# Shield-Proteco.net
KiCad netlist of a schematic drawn in EAGLE
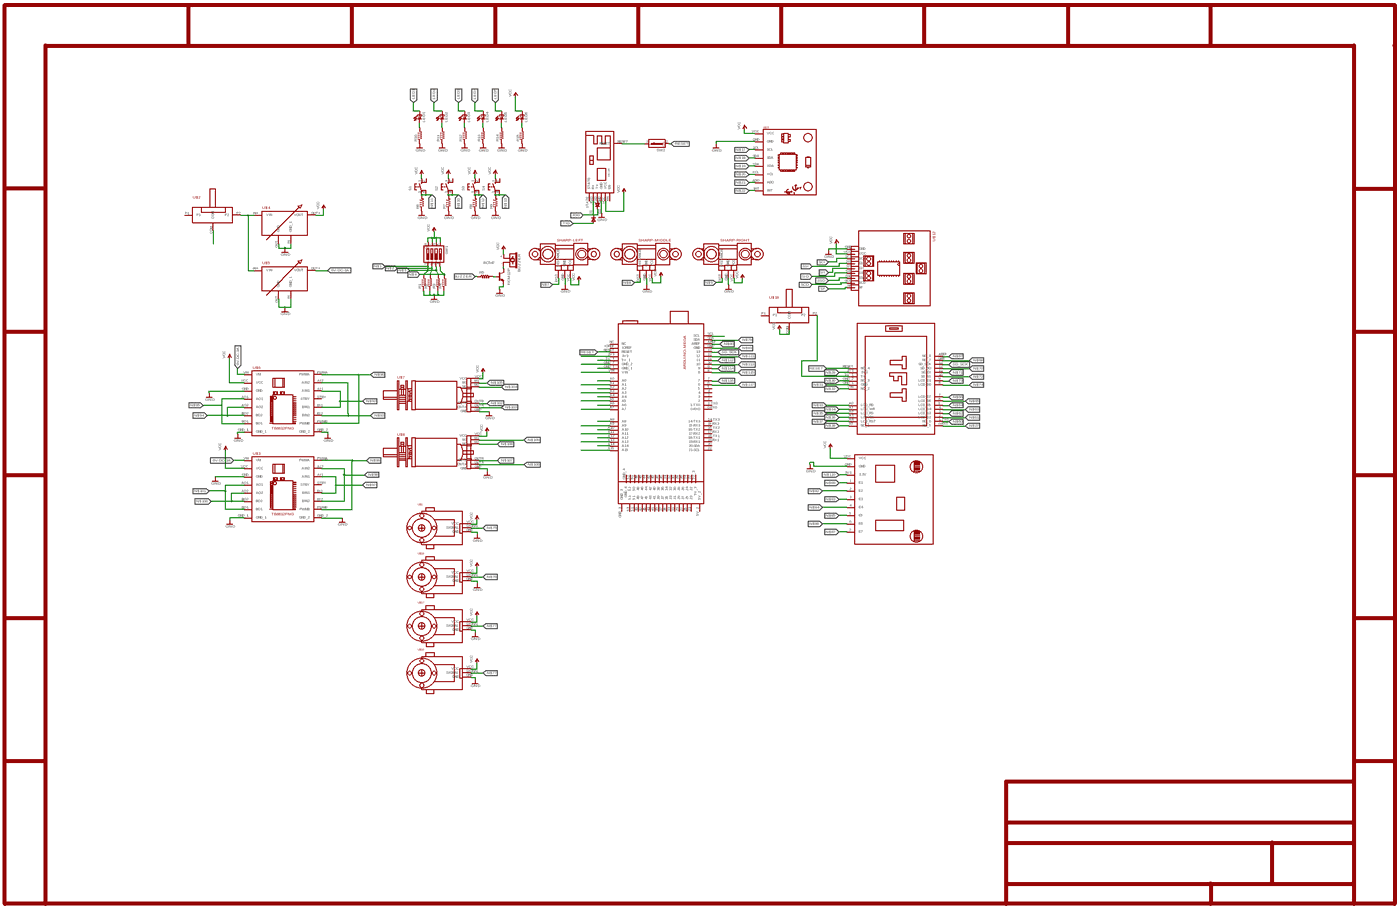
[diagram p0: schematic, sheet 1, overview]
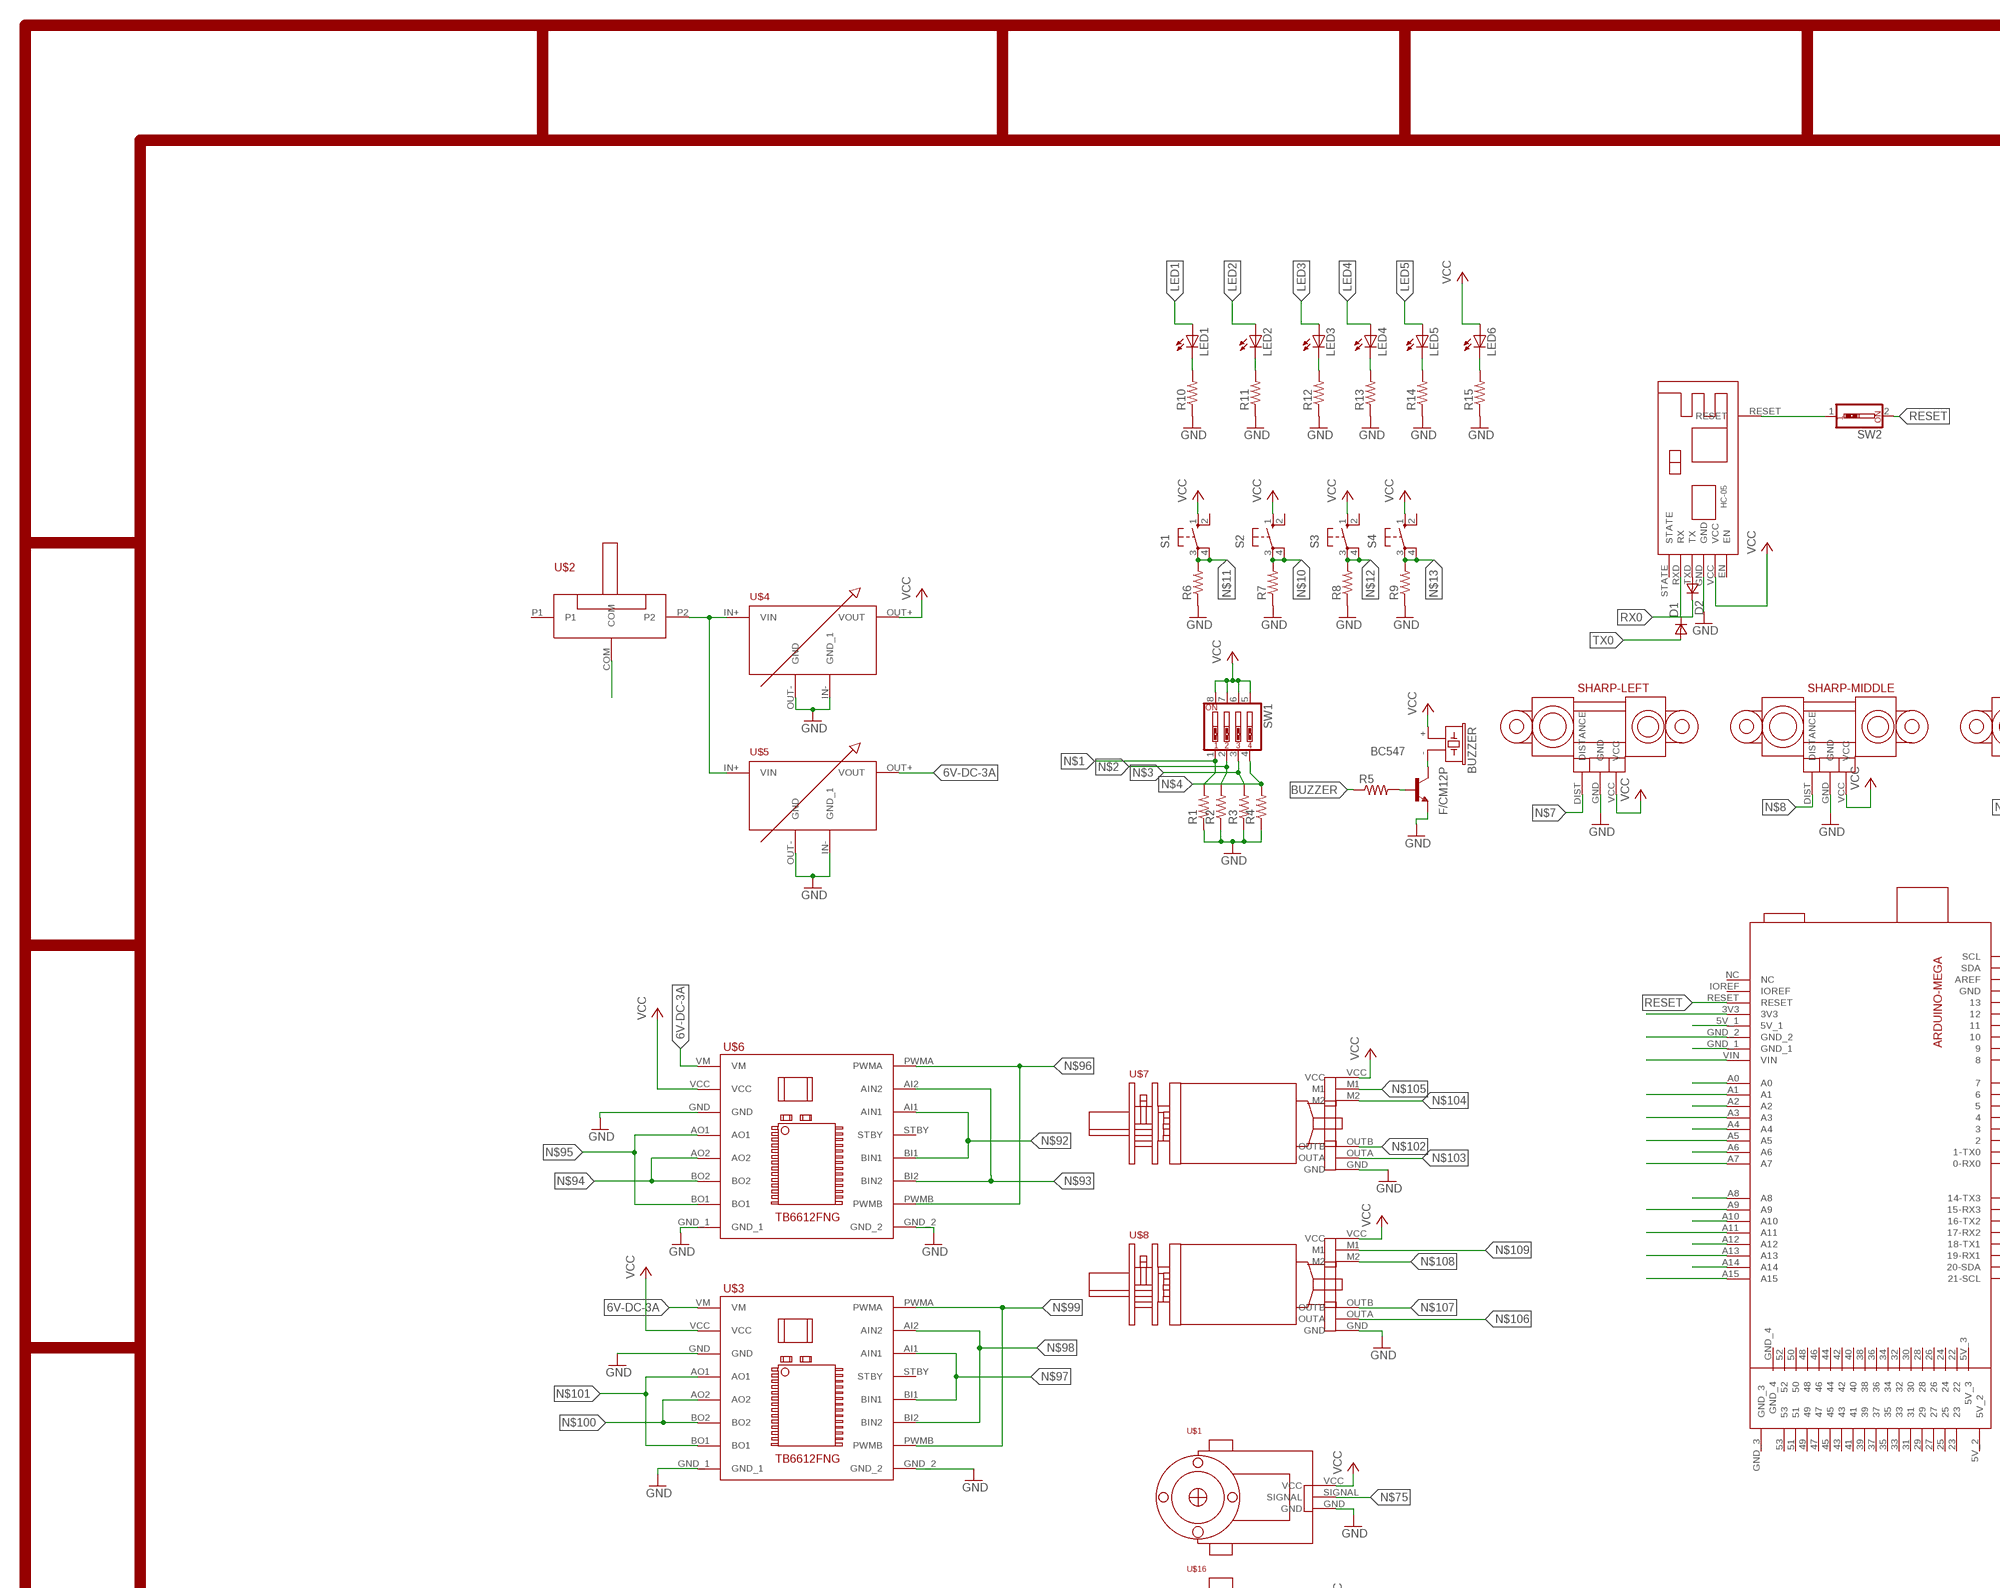
[diagram p1: schematic, sheet 1, part 1 of 4]
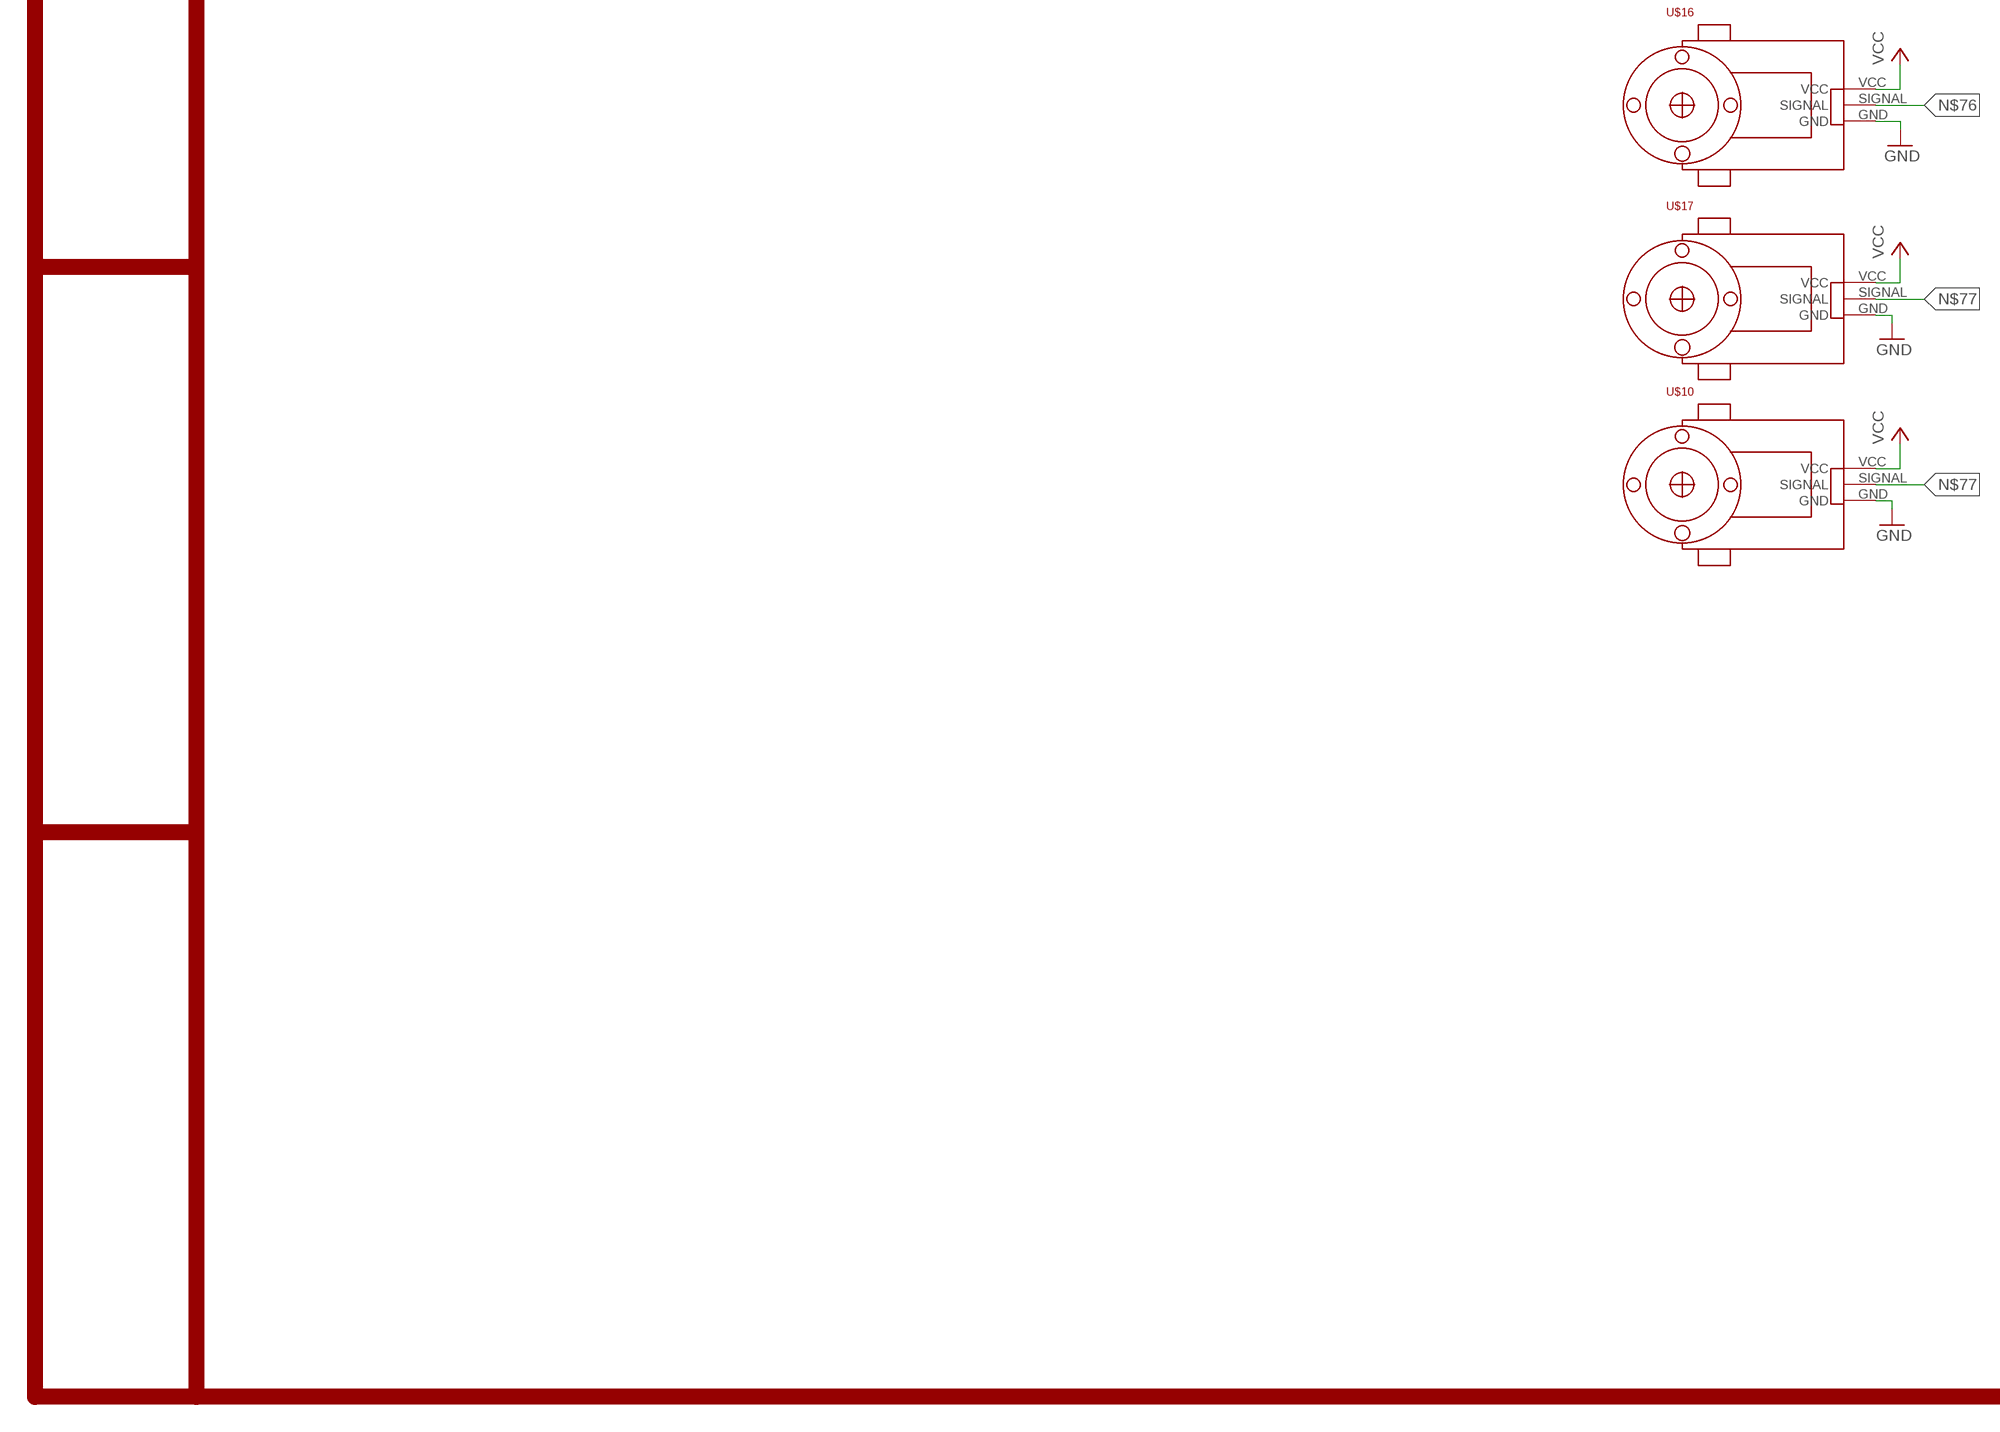
[diagram p2: schematic, sheet 1, part 2 of 4]
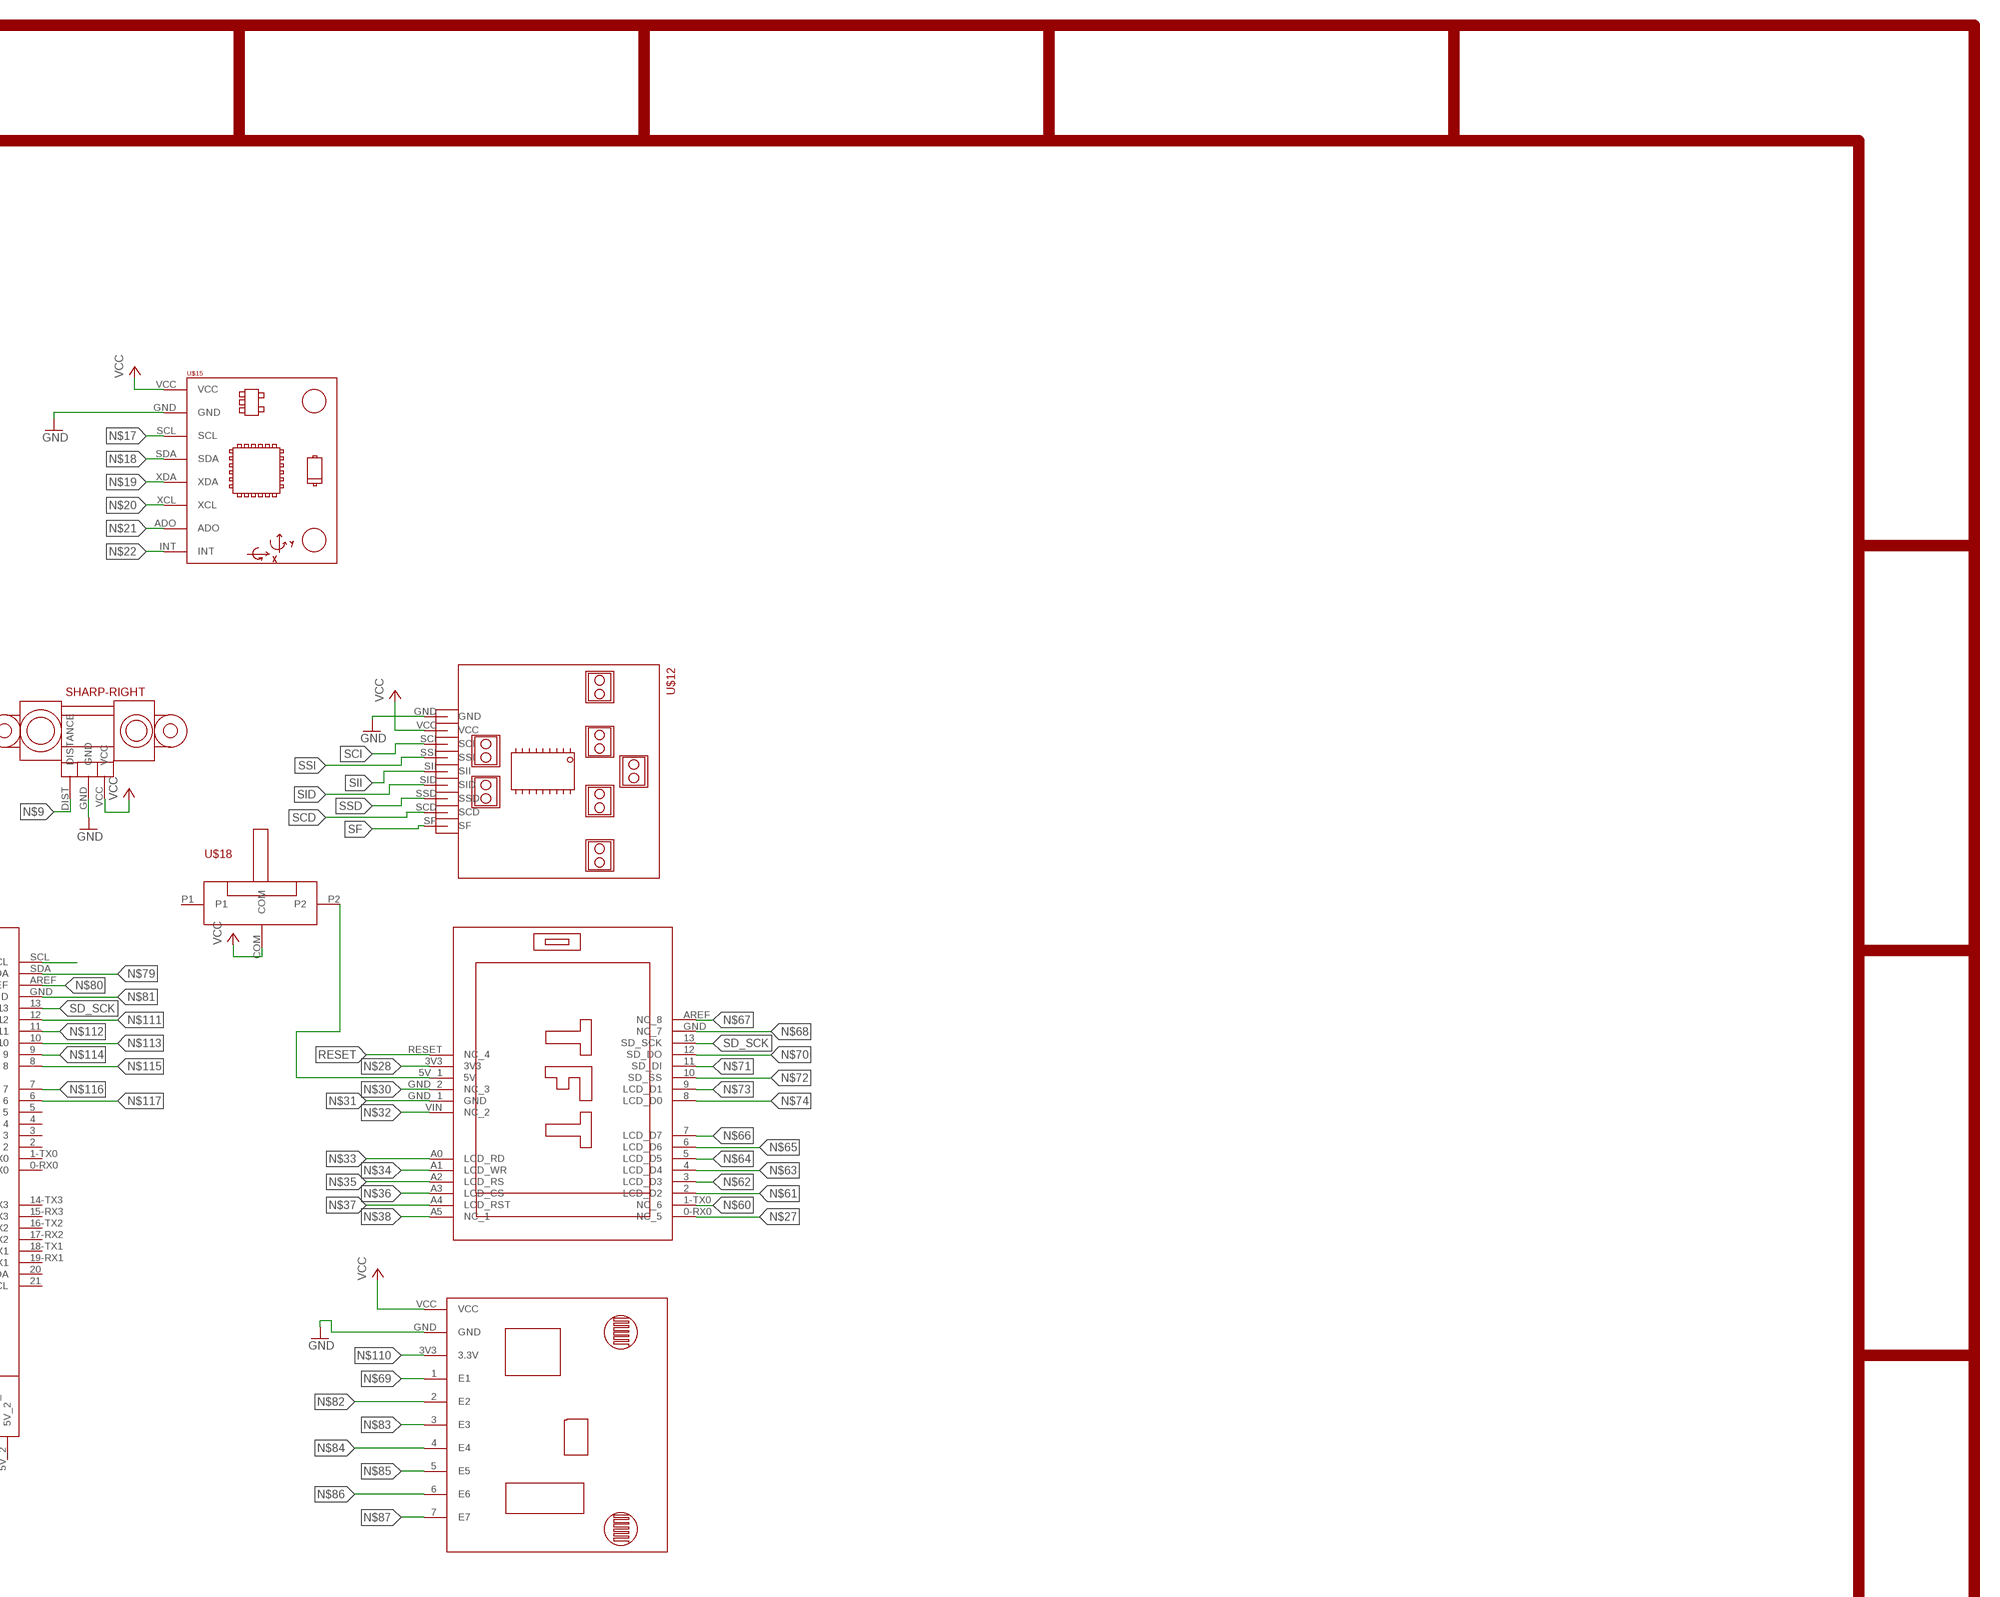
[diagram p3: schematic, sheet 1, part 3 of 4]
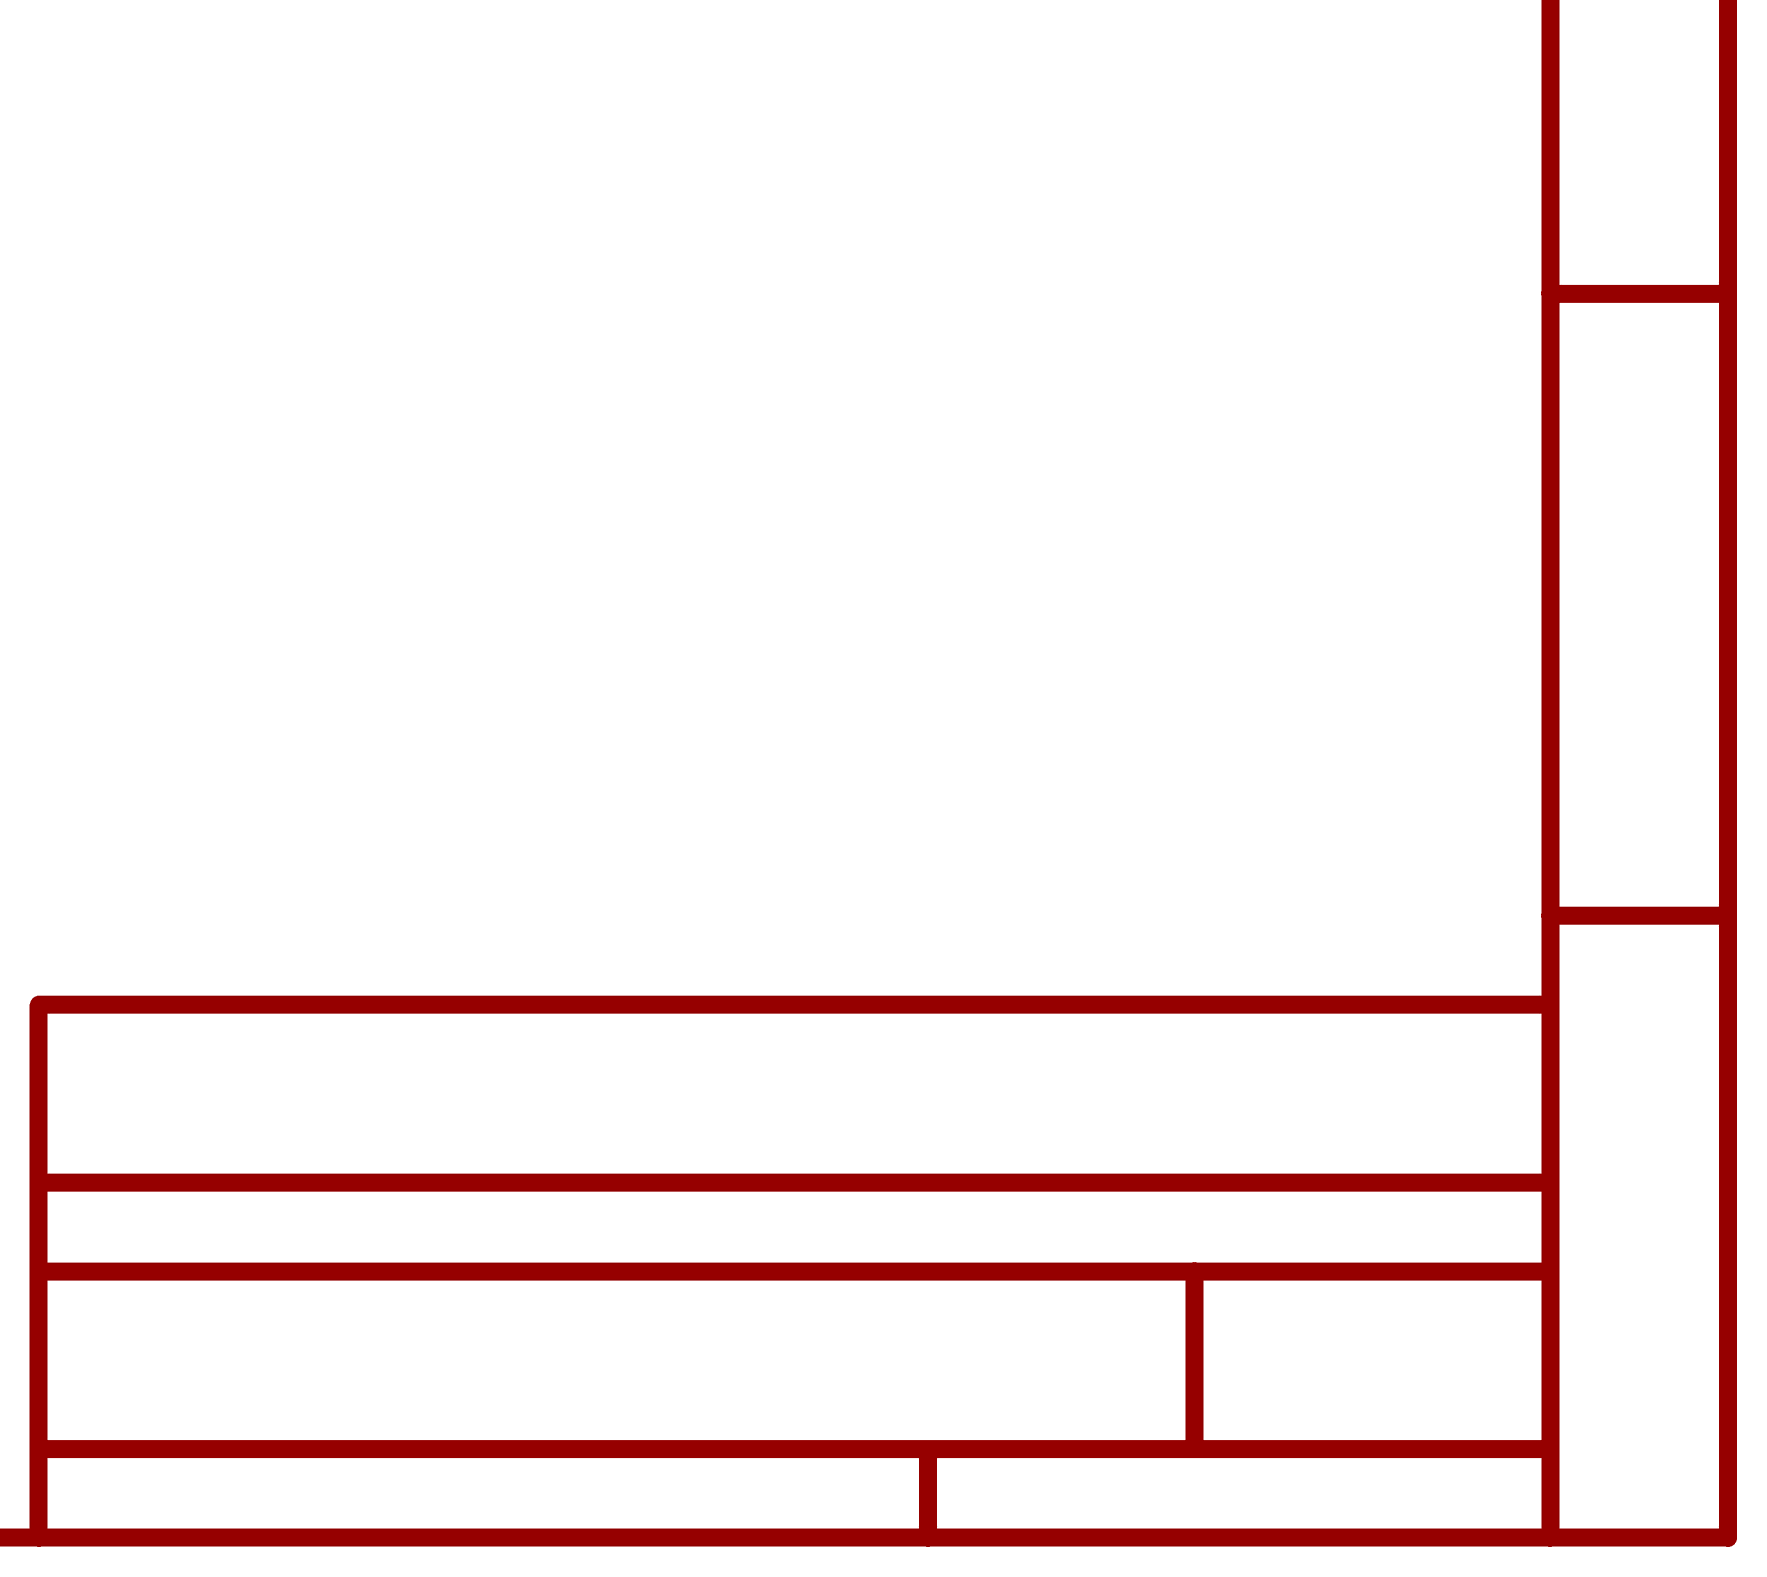
[diagram p4: schematic, sheet 1, part 4 of 4]

(export (version "E")
  (design (tool "Eeschema 10.0.6"))
  (components
    (comp (ref "ARDUINO-MEGA")
      (value "ARDUINO_MEGA")
      (footprint "eagle-import:ARDUINO-MEGA")
      (libsource (lib "eagle-import") (part "ARDUINO_MEGA"))
    )
    (comp (ref "BC547")
      (value "BC547-NPN-TO92-CBE")
      (footprint "eagle-import:TO92-CBE")
      (libsource (lib "eagle-import") (part "-NPN-TO92-CBEBC547"))
    )
    (comp (ref "BUZZER")
      (value "F/CM12P")
      (footprint "eagle-import:F_CM12P")
      (libsource (lib "eagle-import") (part "F/CM12P"))
    )
    (comp (ref "D1")
      (value "DSOD323")
      (footprint "eagle-import:SOD323")
      (fields (field (name "MPN") "CDSOD323-T05C"))
      (libsource (lib "eagle-import") (part "DSOD323"))
    )
    (comp (ref "D2")
      (value "DSOD323")
      (footprint "eagle-import:SOD323")
      (fields (field (name "MPN") "CDSOD323-T05C"))
      (libsource (lib "eagle-import") (part "DSOD323"))
    )
    (comp (ref "HC-05")
      (value "HC-05-PROG")
      (footprint "eagle-import:HC-05-PROG")
      (libsource (lib "eagle-import") (part "HC-05-PROG"))
    )
    (comp (ref "LED1")
      (value "LEDCHIPLED_1206")
      (footprint "eagle-import:CHIPLED_1206")
      (libsource (lib "eagle-import") (part "LEDCHIPLED_1206"))
    )
    (comp (ref "LED2")
      (value "LEDCHIPLED_1206")
      (footprint "eagle-import:CHIPLED_1206")
      (libsource (lib "eagle-import") (part "LEDCHIPLED_1206"))
    )
    (comp (ref "LED3")
      (value "LEDCHIPLED_1206")
      (footprint "eagle-import:CHIPLED_1206")
      (libsource (lib "eagle-import") (part "LEDCHIPLED_1206"))
    )
    (comp (ref "LED4")
      (value "LEDCHIPLED_1206")
      (footprint "eagle-import:CHIPLED_1206")
      (libsource (lib "eagle-import") (part "LEDCHIPLED_1206"))
    )
    (comp (ref "LED5")
      (value "LEDCHIPLED_1206")
      (footprint "eagle-import:CHIPLED_1206")
      (libsource (lib "eagle-import") (part "LEDCHIPLED_1206"))
    )
    (comp (ref "LED6")
      (value "LEDCHIPLED_1206")
      (footprint "eagle-import:CHIPLED_1206")
      (libsource (lib "eagle-import") (part "LEDCHIPLED_1206"))
    )
    (comp (ref "R1")
      (value "R-US_M1206")
      (footprint "eagle-import:M1206")
      (libsource (lib "eagle-import") (part "R-US_M1206"))
    )
    (comp (ref "R2")
      (value "R-US_M1206")
      (footprint "eagle-import:M1206")
      (libsource (lib "eagle-import") (part "R-US_M1206"))
    )
    (comp (ref "R3")
      (value "R-US_M1206")
      (footprint "eagle-import:M1206")
      (libsource (lib "eagle-import") (part "R-US_M1206"))
    )
    (comp (ref "R4")
      (value "R-US_M1206")
      (footprint "eagle-import:M1206")
      (libsource (lib "eagle-import") (part "R-US_M1206"))
    )
    (comp (ref "R5")
      (value "R-US_M1206")
      (footprint "eagle-import:M1206")
      (libsource (lib "eagle-import") (part "R-US_M1206"))
    )
    (comp (ref "R6")
      (value "R-US_M1206")
      (footprint "eagle-import:M1206")
      (libsource (lib "eagle-import") (part "R-US_M1206"))
    )
    (comp (ref "R7")
      (value "R-US_M1206")
      (footprint "eagle-import:M1206")
      (libsource (lib "eagle-import") (part "R-US_M1206"))
    )
    (comp (ref "R8")
      (value "R-US_M1206")
      (footprint "eagle-import:M1206")
      (libsource (lib "eagle-import") (part "R-US_M1206"))
    )
    (comp (ref "R9")
      (value "R-US_M1206")
      (footprint "eagle-import:M1206")
      (libsource (lib "eagle-import") (part "R-US_M1206"))
    )
    (comp (ref "R10")
      (value "R-US_M1206")
      (footprint "eagle-import:M1206")
      (libsource (lib "eagle-import") (part "R-US_M1206"))
    )
    (comp (ref "R11")
      (value "R-US_M1206")
      (footprint "eagle-import:M1206")
      (libsource (lib "eagle-import") (part "R-US_M1206"))
    )
    (comp (ref "R12")
      (value "R-US_M1206")
      (footprint "eagle-import:M1206")
      (libsource (lib "eagle-import") (part "R-US_M1206"))
    )
    (comp (ref "R13")
      (value "R-US_M1206")
      (footprint "eagle-import:M1206")
      (libsource (lib "eagle-import") (part "R-US_M1206"))
    )
    (comp (ref "R14")
      (value "R-US_M1206")
      (footprint "eagle-import:M1206")
      (libsource (lib "eagle-import") (part "R-US_M1206"))
    )
    (comp (ref "R15")
      (value "R-US_M1206")
      (footprint "eagle-import:M1206")
      (libsource (lib "eagle-import") (part "R-US_M1206"))
    )
    (comp (ref "S1")
      (value "10-XX")
      (footprint "eagle-import:B3F-10XX")
      (fields (field (name "MPN") "B3F-1000"))
      (libsource (lib "eagle-import") (part "10-XX"))
    )
    (comp (ref "S2")
      (value "10-XX")
      (footprint "eagle-import:B3F-10XX")
      (fields (field (name "MPN") "B3F-1000"))
      (libsource (lib "eagle-import") (part "10-XX"))
    )
    (comp (ref "S3")
      (value "10-XX")
      (footprint "eagle-import:B3F-10XX")
      (fields (field (name "MPN") "B3F-1000"))
      (libsource (lib "eagle-import") (part "10-XX"))
    )
    (comp (ref "S4")
      (value "10-XX")
      (footprint "eagle-import:B3F-10XX")
      (fields (field (name "MPN") "B3F-1000"))
      (libsource (lib "eagle-import") (part "10-XX"))
    )
    (comp (ref "SHARP-LEFT")
      (value "SHARP")
      (footprint "eagle-import:SHARP")
      (libsource (lib "eagle-import") (part "SHARP"))
    )
    (comp (ref "SHARP-MIDDLE")
      (value "SHARP")
      (footprint "eagle-import:SHARP")
      (libsource (lib "eagle-import") (part "SHARP"))
    )
    (comp (ref "SHARP-RIGHT")
      (value "SHARP")
      (footprint "eagle-import:SHARP")
      (libsource (lib "eagle-import") (part "SHARP"))
    )
    (comp (ref "SW1")
      (value "SW_DIP-4")
      (footprint "eagle-import:EDG-04")
      (libsource (lib "eagle-import") (part "SW_DIP-4"))
    )
    (comp (ref "SW2")
      (value "SW_DIP-1")
      (footprint "eagle-import:EDG-01")
      (libsource (lib "eagle-import") (part "SW_DIP-1"))
    )
    (comp (ref "U$1")
      (value "SERVOMOTORES")
      (footprint "eagle-import:SERVO")
      (libsource (lib "eagle-import") (part "SERVOMOTORES"))
    )
    (comp (ref "U$2")
      (value "SLIDE-3")
      (footprint "eagle-import:SLIDE-3")
      (libsource (lib "eagle-import") (part "SLIDE-3"))
    )
    (comp (ref "U$3")
      (value "TB6612FNG")
      (footprint "eagle-import:TB6612FNG")
      (libsource (lib "eagle-import") (part "TB6612FNG"))
    )
    (comp (ref "U$4")
      (value "STEPDOWN-DC-DC")
      (footprint "eagle-import:STEPDOWN-DC-DC")
      (libsource (lib "eagle-import") (part "STEPDOWN-DC-DC"))
    )
    (comp (ref "U$5")
      (value "STEPDOWN-DC-DC")
      (footprint "eagle-import:STEPDOWN-DC-DC")
      (libsource (lib "eagle-import") (part "STEPDOWN-DC-DC"))
    )
    (comp (ref "U$6")
      (value "TB6612FNG")
      (footprint "eagle-import:TB6612FNG")
      (libsource (lib "eagle-import") (part "TB6612FNG"))
    )
    (comp (ref "U$7")
      (value "POLOLU-MICROMOTOR")
      (footprint "eagle-import:JST")
      (libsource (lib "eagle-import") (part "POLOLU-MICROMOTOR"))
    )
    (comp (ref "U$8")
      (value "POLOLU-MICROMOTOR")
      (footprint "eagle-import:JST")
      (libsource (lib "eagle-import") (part "POLOLU-MICROMOTOR"))
    )
    (comp (ref "U$9")
      (value "SENSOR-MISCELANEOUS")
      (footprint "eagle-import:SENSOR-MISCELANEOUS")
      (libsource (lib "eagle-import") (part "SENSOR-MISCELANEOUS"))
    )
    (comp (ref "U$10")
      (value "SERVOMOTORES")
      (footprint "eagle-import:SERVO")
      (libsource (lib "eagle-import") (part "SERVOMOTORES"))
    )
    (comp (ref "U$12")
      (value "CNY70-ARRAY")
      (footprint "eagle-import:CNY70-ARRAY")
      (libsource (lib "eagle-import") (part "CNY70-ARRAY"))
    )
    (comp (ref "U$14")
      (value "TFT_ARDUINO-UNO-MEGA")
      (footprint "eagle-import:TFT-ARDUINO-UNO-MEGA")
      (libsource (lib "eagle-import") (part "TFT_ARDUINO-UNO-MEGA"))
    )
    (comp (ref "U$15")
      (value "ACELEROMETER-MPU6050-JST")
      (footprint "eagle-import:ACELEROMETER-MPU6050-JST")
      (libsource (lib "eagle-import") (part "ACELEROMETER-MPU6050-JST"))
    )
    (comp (ref "U$16")
      (value "SERVOMOTORES")
      (footprint "eagle-import:SERVO")
      (libsource (lib "eagle-import") (part "SERVOMOTORES"))
    )
    (comp (ref "U$17")
      (value "SERVOMOTORES")
      (footprint "eagle-import:SERVO")
      (libsource (lib "eagle-import") (part "SERVOMOTORES"))
    )
    (comp (ref "U$18")
      (value "SLIDE-3")
      (footprint "eagle-import:SLIDE-3")
      (libsource (lib "eagle-import") (part "SLIDE-3"))
    )
  )
  (nets
    (net (code "1") (name "6V-DC-3A") (class "Default")
      (node (ref "U$3") (pin "VM") (pinfunction "VM_VM") (pintype "bidirectional"))
      (node (ref "U$5") (pin "OUT+") (pinfunction "VOUT_OUT+") (pintype "bidirectional"))
      (node (ref "U$6") (pin "VM") (pinfunction "VM_VM") (pintype "bidirectional"))
    )
    (net (code "2") (name "BUZZER") (class "Default")
      (node (ref "R5") (pin "1") (pinfunction "1_1") (pintype "passive"))
    )
    (net (code "3") (name "GND") (class "Default")
      (node (ref "BC547") (pin "E") (pinfunction "E_E") (pintype "passive"))
      (node (ref "HC-05") (pin "GND") (pinfunction "GND_GND") (pintype "bidirectional"))
      (node (ref "R1") (pin "1") (pinfunction "1_1") (pintype "passive"))
      (node (ref "R10") (pin "1") (pinfunction "1_1") (pintype "passive"))
      (node (ref "R11") (pin "1") (pinfunction "1_1") (pintype "passive"))
      (node (ref "R12") (pin "1") (pinfunction "1_1") (pintype "passive"))
      (node (ref "R13") (pin "1") (pinfunction "1_1") (pintype "passive"))
      (node (ref "R14") (pin "1") (pinfunction "1_1") (pintype "passive"))
      (node (ref "R15") (pin "1") (pinfunction "1_1") (pintype "passive"))
      (node (ref "R2") (pin "1") (pinfunction "1_1") (pintype "passive"))
      (node (ref "R3") (pin "1") (pinfunction "1_1") (pintype "passive"))
      (node (ref "R4") (pin "1") (pinfunction "1_1") (pintype "passive"))
      (node (ref "R6") (pin "1") (pinfunction "1_1") (pintype "passive"))
      (node (ref "R7") (pin "1") (pinfunction "1_1") (pintype "passive"))
      (node (ref "R8") (pin "1") (pinfunction "1_1") (pintype "passive"))
      (node (ref "R9") (pin "1") (pinfunction "1_1") (pintype "passive"))
      (node (ref "SHARP-LEFT") (pin "GND") (pinfunction "GND_GND") (pintype "bidirectional"))
      (node (ref "SHARP-MIDDLE") (pin "GND") (pinfunction "GND_GND") (pintype "bidirectional"))
      (node (ref "SHARP-RIGHT") (pin "GND") (pinfunction "GND_GND") (pintype "bidirectional"))
      (node (ref "U$1") (pin "GND") (pinfunction "GND_GND") (pintype "bidirectional"))
      (node (ref "U$10") (pin "GND") (pinfunction "GND_GND") (pintype "bidirectional"))
      (node (ref "U$12") (pin "GND") (pinfunction "GND_GND") (pintype "bidirectional"))
      (node (ref "U$15") (pin "GND") (pinfunction "GND_GND") (pintype "bidirectional"))
      (node (ref "U$16") (pin "GND") (pinfunction "GND_GND") (pintype "bidirectional"))
      (node (ref "U$17") (pin "GND") (pinfunction "GND_GND") (pintype "bidirectional"))
      (node (ref "U$3") (pin "GND") (pinfunction "GND_GND") (pintype "bidirectional"))
      (node (ref "U$3") (pin "GND_1") (pinfunction "GND_1_GND_1") (pintype "bidirectional"))
      (node (ref "U$3") (pin "GND_2") (pinfunction "GND_2_GND_2") (pintype "bidirectional"))
      (node (ref "U$4") (pin "IN-") (pinfunction "GND_1_IN-") (pintype "bidirectional"))
      (node (ref "U$4") (pin "OUT-") (pinfunction "GND_OUT-") (pintype "bidirectional"))
      (node (ref "U$5") (pin "IN-") (pinfunction "GND_1_IN-") (pintype "bidirectional"))
      (node (ref "U$5") (pin "OUT-") (pinfunction "GND_OUT-") (pintype "bidirectional"))
      (node (ref "U$6") (pin "GND") (pinfunction "GND_GND") (pintype "bidirectional"))
      (node (ref "U$6") (pin "GND_1") (pinfunction "GND_1_GND_1") (pintype "bidirectional"))
      (node (ref "U$6") (pin "GND_2") (pinfunction "GND_2_GND_2") (pintype "bidirectional"))
      (node (ref "U$7") (pin "GND") (pinfunction "GND_GND") (pintype "bidirectional"))
      (node (ref "U$8") (pin "GND") (pinfunction "GND_GND") (pintype "bidirectional"))
      (node (ref "U$9") (pin "GND") (pinfunction "GND_GND") (pintype "bidirectional"))
    )
    (net (code "4") (name "LED1") (class "Default")
      (node (ref "LED1") (pin "A") (pinfunction "A_A") (pintype "passive"))
    )
    (net (code "5") (name "LED2") (class "Default")
      (node (ref "LED2") (pin "A") (pinfunction "A_A") (pintype "passive"))
    )
    (net (code "6") (name "LED3") (class "Default")
      (node (ref "LED3") (pin "A") (pinfunction "A_A") (pintype "passive"))
    )
    (net (code "7") (name "LED4") (class "Default")
      (node (ref "LED4") (pin "A") (pinfunction "A_A") (pintype "passive"))
    )
    (net (code "8") (name "LED5") (class "Default")
      (node (ref "LED5") (pin "A") (pinfunction "A_A") (pintype "passive"))
    )
    (net (code "9") (name "N$1") (class "Default")
      (node (ref "R1") (pin "2") (pinfunction "2_2") (pintype "passive"))
      (node (ref "SW1") (pin "1") (pinfunction "1_1") (pintype "passive"))
    )
    (net (code "10") (name "N$2") (class "Default")
      (node (ref "R2") (pin "2") (pinfunction "2_2") (pintype "passive"))
      (node (ref "SW1") (pin "2") (pinfunction "2_2") (pintype "passive"))
    )
    (net (code "11") (name "N$3") (class "Default")
      (node (ref "R3") (pin "2") (pinfunction "2_2") (pintype "passive"))
      (node (ref "SW1") (pin "3") (pinfunction "3_3") (pintype "passive"))
    )
    (net (code "12") (name "N$4") (class "Default")
      (node (ref "R4") (pin "2") (pinfunction "2_2") (pintype "passive"))
      (node (ref "SW1") (pin "4") (pinfunction "4_4") (pintype "passive"))
    )
    (net (code "13") (name "N$7") (class "Default")
      (node (ref "SHARP-LEFT") (pin "DIST") (pinfunction "DISTANCE_DIST") (pintype "bidirectional"))
    )
    (net (code "14") (name "N$8") (class "Default")
      (node (ref "SHARP-MIDDLE") (pin "DIST") (pinfunction "DISTANCE_DIST") (pintype "bidirectional"))
    )
    (net (code "15") (name "N$9") (class "Default")
      (node (ref "SHARP-RIGHT") (pin "DIST") (pinfunction "DISTANCE_DIST") (pintype "bidirectional"))
    )
    (net (code "16") (name "N$10") (class "Default")
      (node (ref "R7") (pin "2") (pinfunction "2_2") (pintype "passive"))
      (node (ref "S2") (pin "3") (pinfunction "P_3") (pintype "passive"))
      (node (ref "S2") (pin "4") (pinfunction "P1_4") (pintype "passive"))
    )
    (net (code "17") (name "N$11") (class "Default")
      (node (ref "R6") (pin "2") (pinfunction "2_2") (pintype "passive"))
      (node (ref "S1") (pin "3") (pinfunction "P_3") (pintype "passive"))
      (node (ref "S1") (pin "4") (pinfunction "P1_4") (pintype "passive"))
    )
    (net (code "18") (name "N$12") (class "Default")
      (node (ref "R8") (pin "2") (pinfunction "2_2") (pintype "passive"))
      (node (ref "S3") (pin "3") (pinfunction "P_3") (pintype "passive"))
      (node (ref "S3") (pin "4") (pinfunction "P1_4") (pintype "passive"))
    )
    (net (code "19") (name "N$13") (class "Default")
      (node (ref "R9") (pin "2") (pinfunction "2_2") (pintype "passive"))
      (node (ref "S4") (pin "3") (pinfunction "P_3") (pintype "passive"))
      (node (ref "S4") (pin "4") (pinfunction "P1_4") (pintype "passive"))
    )
    (net (code "20") (name "N$17") (class "Default")
      (node (ref "U$15") (pin "SCL") (pinfunction "SCL_SCL") (pintype "bidirectional"))
    )
    (net (code "21") (name "N$18") (class "Default")
      (node (ref "U$15") (pin "SDA") (pinfunction "SDA_SDA") (pintype "bidirectional"))
    )
    (net (code "22") (name "N$19") (class "Default")
      (node (ref "U$15") (pin "XDA") (pinfunction "XDA_XDA") (pintype "bidirectional"))
    )
    (net (code "23") (name "N$20") (class "Default")
      (node (ref "U$15") (pin "XCL") (pinfunction "XCL_XCL") (pintype "bidirectional"))
    )
    (net (code "24") (name "N$21") (class "Default")
      (node (ref "U$15") (pin "ADO") (pinfunction "ADO_ADO") (pintype "bidirectional"))
    )
    (net (code "25") (name "N$22") (class "Default")
      (node (ref "U$15") (pin "INT") (pinfunction "INT_INT") (pintype "bidirectional"))
    )
    (net (code "26") (name "N$27") (class "Default")
      (node (ref "U$14") (pin "0-RX0") (pinfunction "NC_5_0-RX0") (pintype "bidirectional"))
    )
    (net (code "27") (name "N$28") (class "Default")
      (node (ref "U$14") (pin "3V3") (pinfunction "3V3_3V3") (pintype "bidirectional"))
    )
    (net (code "28") (name "N$30") (class "Default")
      (node (ref "U$14") (pin "GND_2") (pinfunction "NC_3_GND_2") (pintype "bidirectional"))
    )
    (net (code "29") (name "N$31") (class "Default")
      (node (ref "U$14") (pin "GND_1") (pinfunction "GND_GND_1") (pintype "bidirectional"))
    )
    (net (code "30") (name "N$32") (class "Default")
      (node (ref "U$14") (pin "VIN") (pinfunction "NC_2_VIN") (pintype "bidirectional"))
    )
    (net (code "31") (name "N$33") (class "Default")
      (node (ref "U$14") (pin "A0") (pinfunction "LCD_RD_A0") (pintype "bidirectional"))
    )
    (net (code "32") (name "N$34") (class "Default")
      (node (ref "U$14") (pin "A1") (pinfunction "LCD_WR_A1") (pintype "bidirectional"))
    )
    (net (code "33") (name "N$35") (class "Default")
      (node (ref "U$14") (pin "A2") (pinfunction "LCD_RS_A2") (pintype "bidirectional"))
    )
    (net (code "34") (name "N$36") (class "Default")
      (node (ref "U$14") (pin "A3") (pinfunction "LCD_CS_A3") (pintype "bidirectional"))
    )
    (net (code "35") (name "N$37") (class "Default")
      (node (ref "U$14") (pin "A4") (pinfunction "LCD_RST_A4") (pintype "bidirectional"))
    )
    (net (code "36") (name "N$38") (class "Default")
      (node (ref "U$14") (pin "A5") (pinfunction "NC_1_A5") (pintype "bidirectional"))
    )
    (net (code "37") (name "N$60") (class "Default")
      (node (ref "U$14") (pin "1-TX0") (pinfunction "NC_6_1-TX0") (pintype "bidirectional"))
    )
    (net (code "38") (name "N$61") (class "Default")
      (node (ref "U$14") (pin "2") (pinfunction "LCD_D2_2") (pintype "bidirectional"))
    )
    (net (code "39") (name "N$62") (class "Default")
      (node (ref "U$14") (pin "3") (pinfunction "LCD_D3_3") (pintype "bidirectional"))
    )
    (net (code "40") (name "N$63") (class "Default")
      (node (ref "U$14") (pin "4") (pinfunction "LCD_D4_4") (pintype "bidirectional"))
    )
    (net (code "41") (name "N$64") (class "Default")
      (node (ref "U$14") (pin "5") (pinfunction "LCD_D5_5") (pintype "bidirectional"))
    )
    (net (code "42") (name "N$65") (class "Default")
      (node (ref "U$14") (pin "6") (pinfunction "LCD_D6_6") (pintype "bidirectional"))
    )
    (net (code "43") (name "N$66") (class "Default")
      (node (ref "U$14") (pin "7") (pinfunction "LCD_D7_7") (pintype "bidirectional"))
    )
    (net (code "44") (name "N$67") (class "Default")
      (node (ref "U$14") (pin "AREF") (pinfunction "NC_8_AREF") (pintype "bidirectional"))
    )
    (net (code "45") (name "N$68") (class "Default")
      (node (ref "U$14") (pin "GND") (pinfunction "NC_7_GND") (pintype "bidirectional"))
    )
    (net (code "46") (name "N$69") (class "Default")
      (node (ref "U$9") (pin "1") (pinfunction "E1_1") (pintype "bidirectional"))
    )
    (net (code "47") (name "N$70") (class "Default")
      (node (ref "U$14") (pin "12") (pinfunction "SD_DO_12") (pintype "bidirectional"))
    )
    (net (code "48") (name "N$71") (class "Default")
      (node (ref "U$14") (pin "11") (pinfunction "SD_DI_11") (pintype "bidirectional"))
    )
    (net (code "49") (name "N$72") (class "Default")
      (node (ref "U$14") (pin "10") (pinfunction "SD_SS_10") (pintype "bidirectional"))
    )
    (net (code "50") (name "N$73") (class "Default")
      (node (ref "U$14") (pin "9") (pinfunction "LCD_D1_9") (pintype "bidirectional"))
    )
    (net (code "51") (name "N$74") (class "Default")
      (node (ref "U$14") (pin "8") (pinfunction "LCD_D0_8") (pintype "bidirectional"))
    )
    (net (code "52") (name "N$75") (class "Default")
      (node (ref "U$1") (pin "SIGNAL") (pinfunction "SIGNAL_SIGNAL") (pintype "bidirectional"))
    )
    (net (code "53") (name "N$76") (class "Default")
      (node (ref "U$16") (pin "SIGNAL") (pinfunction "SIGNAL_SIGNAL") (pintype "bidirectional"))
    )
    (net (code "54") (name "N$77") (class "Default")
      (node (ref "U$10") (pin "SIGNAL") (pinfunction "SIGNAL_SIGNAL") (pintype "bidirectional"))
      (node (ref "U$17") (pin "SIGNAL") (pinfunction "SIGNAL_SIGNAL") (pintype "bidirectional"))
    )
    (net (code "55") (name "N$79") (class "Default")
      (node (ref "ARDUINO-MEGA") (pin "SDA") (pinfunction "SDA_SDA") (pintype "bidirectional"))
    )
    (net (code "56") (name "N$80") (class "Default")
      (node (ref "ARDUINO-MEGA") (pin "AREF") (pinfunction "AREF_AREF") (pintype "bidirectional"))
    )
    (net (code "57") (name "N$81") (class "Default")
      (node (ref "ARDUINO-MEGA") (pin "GND") (pinfunction "GND_GND") (pintype "bidirectional"))
    )
    (net (code "58") (name "N$82") (class "Default")
      (node (ref "U$9") (pin "2") (pinfunction "E2_2") (pintype "bidirectional"))
    )
    (net (code "59") (name "N$83") (class "Default")
      (node (ref "U$9") (pin "3") (pinfunction "E3_3") (pintype "bidirectional"))
    )
    (net (code "60") (name "N$84") (class "Default")
      (node (ref "U$9") (pin "4") (pinfunction "E4_4") (pintype "bidirectional"))
    )
    (net (code "61") (name "N$85") (class "Default")
      (node (ref "U$9") (pin "5") (pinfunction "E5_5") (pintype "bidirectional"))
    )
    (net (code "62") (name "N$86") (class "Default")
      (node (ref "U$9") (pin "6") (pinfunction "E6_6") (pintype "bidirectional"))
    )
    (net (code "63") (name "N$87") (class "Default")
      (node (ref "U$9") (pin "7") (pinfunction "E7_7") (pintype "bidirectional"))
    )
    (net (code "64") (name "N$92") (class "Default")
      (node (ref "U$6") (pin "AI1") (pinfunction "AIN1_AI1") (pintype "bidirectional"))
      (node (ref "U$6") (pin "BI1") (pinfunction "BIN1_BI1") (pintype "bidirectional"))
    )
    (net (code "65") (name "N$93") (class "Default")
      (node (ref "U$6") (pin "AI2") (pinfunction "AIN2_AI2") (pintype "bidirectional"))
      (node (ref "U$6") (pin "BI2") (pinfunction "BIN2_BI2") (pintype "bidirectional"))
    )
    (net (code "66") (name "N$94") (class "Default")
      (node (ref "U$6") (pin "AO2") (pinfunction "AO2_AO2") (pintype "bidirectional"))
      (node (ref "U$6") (pin "BO2") (pinfunction "BO2_BO2") (pintype "bidirectional"))
    )
    (net (code "67") (name "N$95") (class "Default")
      (node (ref "U$6") (pin "AO1") (pinfunction "AO1_AO1") (pintype "bidirectional"))
      (node (ref "U$6") (pin "BO1") (pinfunction "BO1_BO1") (pintype "bidirectional"))
    )
    (net (code "68") (name "N$96") (class "Default")
      (node (ref "U$6") (pin "PWMA") (pinfunction "PWMA_PWMA") (pintype "bidirectional"))
      (node (ref "U$6") (pin "PWMB") (pinfunction "PWMB_PWMB") (pintype "bidirectional"))
    )
    (net (code "69") (name "N$97") (class "Default")
      (node (ref "U$3") (pin "AI1") (pinfunction "AIN1_AI1") (pintype "bidirectional"))
      (node (ref "U$3") (pin "BI1") (pinfunction "BIN1_BI1") (pintype "bidirectional"))
    )
    (net (code "70") (name "N$98") (class "Default")
      (node (ref "U$3") (pin "AI2") (pinfunction "AIN2_AI2") (pintype "bidirectional"))
      (node (ref "U$3") (pin "BI2") (pinfunction "BIN2_BI2") (pintype "bidirectional"))
    )
    (net (code "71") (name "N$99") (class "Default")
      (node (ref "U$3") (pin "PWMA") (pinfunction "PWMA_PWMA") (pintype "bidirectional"))
      (node (ref "U$3") (pin "PWMB") (pinfunction "PWMB_PWMB") (pintype "bidirectional"))
    )
    (net (code "72") (name "N$100") (class "Default")
      (node (ref "U$3") (pin "AO2") (pinfunction "AO2_AO2") (pintype "bidirectional"))
      (node (ref "U$3") (pin "BO2") (pinfunction "BO2_BO2") (pintype "bidirectional"))
    )
    (net (code "73") (name "N$101") (class "Default")
      (node (ref "U$3") (pin "AO1") (pinfunction "AO1_AO1") (pintype "bidirectional"))
      (node (ref "U$3") (pin "BO1") (pinfunction "BO1_BO1") (pintype "bidirectional"))
    )
    (net (code "74") (name "N$102") (class "Default")
      (node (ref "U$7") (pin "OUTB") (pinfunction "OUTB_OUTB") (pintype "bidirectional"))
    )
    (net (code "75") (name "N$103") (class "Default")
      (node (ref "U$7") (pin "OUTA") (pinfunction "OUTA_OUTA") (pintype "bidirectional"))
    )
    (net (code "76") (name "N$104") (class "Default")
      (node (ref "U$7") (pin "M2") (pinfunction "M2_M2") (pintype "bidirectional"))
    )
    (net (code "77") (name "N$105") (class "Default")
      (node (ref "U$7") (pin "M1") (pinfunction "M1_M1") (pintype "bidirectional"))
    )
    (net (code "78") (name "N$106") (class "Default")
      (node (ref "U$8") (pin "OUTA") (pinfunction "OUTA_OUTA") (pintype "bidirectional"))
    )
    (net (code "79") (name "N$107") (class "Default")
      (node (ref "U$8") (pin "OUTB") (pinfunction "OUTB_OUTB") (pintype "bidirectional"))
    )
    (net (code "80") (name "N$108") (class "Default")
      (node (ref "U$8") (pin "M2") (pinfunction "M2_M2") (pintype "bidirectional"))
    )
    (net (code "81") (name "N$109") (class "Default")
      (node (ref "U$8") (pin "M1") (pinfunction "M1_M1") (pintype "bidirectional"))
    )
    (net (code "82") (name "N$110") (class "Default")
      (node (ref "U$9") (pin "3V3") (pinfunction "3.3V_3V3") (pintype "bidirectional"))
    )
    (net (code "83") (name "N$111") (class "Default")
      (node (ref "ARDUINO-MEGA") (pin "12") (pinfunction "12_12") (pintype "bidirectional"))
    )
    (net (code "84") (name "N$112") (class "Default")
      (node (ref "ARDUINO-MEGA") (pin "11") (pinfunction "11_11") (pintype "bidirectional"))
    )
    (net (code "85") (name "N$113") (class "Default")
      (node (ref "ARDUINO-MEGA") (pin "10") (pinfunction "10_10") (pintype "bidirectional"))
    )
    (net (code "86") (name "N$114") (class "Default")
      (node (ref "ARDUINO-MEGA") (pin "9") (pinfunction "9_9") (pintype "bidirectional"))
    )
    (net (code "87") (name "N$115") (class "Default")
      (node (ref "ARDUINO-MEGA") (pin "8") (pinfunction "8_8") (pintype "bidirectional"))
    )
    (net (code "88") (name "N$116") (class "Default")
      (node (ref "ARDUINO-MEGA") (pin "7") (pinfunction "7_7") (pintype "bidirectional"))
    )
    (net (code "89") (name "N$117") (class "Default")
      (node (ref "ARDUINO-MEGA") (pin "6") (pinfunction "6_6") (pintype "bidirectional"))
    )
    (net (code "90") (name "Net-(BC547-PadB)") (class "Default")
      (node (ref "BC547") (pin "B") (pinfunction "B_B") (pintype "passive"))
      (node (ref "R5") (pin "2") (pinfunction "2_2") (pintype "passive"))
    )
    (net (code "91") (name "Net-(BUZZER-2)") (class "Default")
      (node (ref "BC547") (pin "C") (pinfunction "C_C") (pintype "passive"))
      (node (ref "BUZZER") (pin "-") (pinfunction "2_-") (pintype "passive"))
    )
    (net (code "92") (name "Net-(D1-C)") (class "Default")
      (node (ref "D1") (pin "1") (pinfunction "C_1") (pintype "passive"))
      (node (ref "HC-05") (pin "RXD") (pinfunction "RX_RXD") (pintype "bidirectional"))
    )
    (net (code "93") (name "Net-(D2-A)") (class "Default")
      (node (ref "D2") (pin "2") (pinfunction "A_2") (pintype "passive"))
      (node (ref "HC-05") (pin "TXD") (pinfunction "TX_TXD") (pintype "bidirectional"))
    )
    (net (code "94") (name "Net-(HC-05-PadRESET)") (class "Default")
      (node (ref "HC-05") (pin "RESET") (pinfunction "RESET_RESET") (pintype "bidirectional"))
      (node (ref "SW2") (pin "1") (pinfunction "1_1") (pintype "passive"))
    )
    (net (code "95") (name "Net-(LED1-PadC)") (class "Default")
      (node (ref "LED1") (pin "C") (pinfunction "C_C") (pintype "passive"))
      (node (ref "R10") (pin "2") (pinfunction "2_2") (pintype "passive"))
    )
    (net (code "96") (name "Net-(LED2-PadC)") (class "Default")
      (node (ref "LED2") (pin "C") (pinfunction "C_C") (pintype "passive"))
      (node (ref "R11") (pin "2") (pinfunction "2_2") (pintype "passive"))
    )
    (net (code "97") (name "Net-(LED3-PadC)") (class "Default")
      (node (ref "LED3") (pin "C") (pinfunction "C_C") (pintype "passive"))
      (node (ref "R12") (pin "2") (pinfunction "2_2") (pintype "passive"))
    )
    (net (code "98") (name "Net-(LED4-PadC)") (class "Default")
      (node (ref "LED4") (pin "C") (pinfunction "C_C") (pintype "passive"))
      (node (ref "R13") (pin "2") (pinfunction "2_2") (pintype "passive"))
    )
    (net (code "99") (name "Net-(LED5-PadC)") (class "Default")
      (node (ref "LED5") (pin "C") (pinfunction "C_C") (pintype "passive"))
      (node (ref "R14") (pin "2") (pinfunction "2_2") (pintype "passive"))
    )
    (net (code "100") (name "Net-(LED6-PadC)") (class "Default")
      (node (ref "LED6") (pin "C") (pinfunction "C_C") (pintype "passive"))
      (node (ref "R15") (pin "2") (pinfunction "2_2") (pintype "passive"))
    )
    (net (code "101") (name "Net-(U$4-VIN)") (class "Default")
      (node (ref "U$2") (pin "P2") (pinfunction "P2_P2") (pintype "bidirectional"))
      (node (ref "U$4") (pin "IN+") (pinfunction "VIN_IN+") (pintype "bidirectional"))
      (node (ref "U$5") (pin "IN+") (pinfunction "VIN_IN+") (pintype "bidirectional"))
    )
    (net (code "102") (name "Net-(U$14-5V)") (class "Default")
      (node (ref "U$14") (pin "5V_1") (pinfunction "5V_5V_1") (pintype "bidirectional"))
      (node (ref "U$18") (pin "P2") (pinfunction "P2_P2") (pintype "bidirectional"))
    )
    (net (code "103") (name "RESET") (class "Default")
      (node (ref "ARDUINO-MEGA") (pin "RESET") (pinfunction "RESET_RESET") (pintype "bidirectional"))
      (node (ref "SW2") (pin "2") (pinfunction "2_2") (pintype "passive"))
      (node (ref "U$14") (pin "RESET") (pinfunction "NC_4_RESET") (pintype "bidirectional"))
    )
    (net (code "104") (name "RX0") (class "Default")
      (node (ref "D2") (pin "1") (pinfunction "C_1") (pintype "passive"))
    )
    (net (code "105") (name "SCD") (class "Default")
      (node (ref "U$12") (pin "SCD") (pinfunction "SCD_SCD") (pintype "bidirectional"))
    )
    (net (code "106") (name "SCI") (class "Default")
      (node (ref "U$12") (pin "SCI") (pinfunction "SCI_SCI") (pintype "bidirectional"))
    )
    (net (code "107") (name "SD_SCK") (class "Default")
      (node (ref "ARDUINO-MEGA") (pin "13") (pinfunction "13_13") (pintype "bidirectional"))
      (node (ref "U$14") (pin "13") (pinfunction "SD_SCK_13") (pintype "bidirectional"))
    )
    (net (code "108") (name "SF") (class "Default")
      (node (ref "U$12") (pin "SF") (pinfunction "SF_SF") (pintype "bidirectional"))
    )
    (net (code "109") (name "SID") (class "Default")
      (node (ref "U$12") (pin "SID") (pinfunction "SID_SID") (pintype "bidirectional"))
    )
    (net (code "110") (name "SII") (class "Default")
      (node (ref "U$12") (pin "SII") (pinfunction "SII_SII") (pintype "bidirectional"))
    )
    (net (code "111") (name "SSD") (class "Default")
      (node (ref "U$12") (pin "SSD") (pinfunction "SSD_SSD") (pintype "bidirectional"))
    )
    (net (code "112") (name "SSI") (class "Default")
      (node (ref "U$12") (pin "SSI") (pinfunction "SSI_SSI") (pintype "bidirectional"))
    )
    (net (code "113") (name "TX0") (class "Default")
      (node (ref "D1") (pin "2") (pinfunction "A_2") (pintype "passive"))
    )
    (net (code "114") (name "VCC") (class "Default")
      (node (ref "BUZZER") (pin "+") (pinfunction "1_+") (pintype "passive"))
      (node (ref "HC-05") (pin "VCC") (pinfunction "VCC_VCC") (pintype "bidirectional"))
      (node (ref "LED6") (pin "A") (pinfunction "A_A") (pintype "passive"))
      (node (ref "S1") (pin "1") (pinfunction "S_1") (pintype "passive"))
      (node (ref "S2") (pin "1") (pinfunction "S_1") (pintype "passive"))
      (node (ref "S3") (pin "1") (pinfunction "S_1") (pintype "passive"))
      (node (ref "S4") (pin "1") (pinfunction "S_1") (pintype "passive"))
      (node (ref "SHARP-LEFT") (pin "VCC") (pinfunction "VCC_VCC") (pintype "bidirectional"))
      (node (ref "SHARP-MIDDLE") (pin "VCC") (pinfunction "VCC_VCC") (pintype "bidirectional"))
      (node (ref "SHARP-RIGHT") (pin "VCC") (pinfunction "VCC_VCC") (pintype "bidirectional"))
      (node (ref "SW1") (pin "5") (pinfunction "5_5") (pintype "passive"))
      (node (ref "SW1") (pin "6") (pinfunction "6_6") (pintype "passive"))
      (node (ref "SW1") (pin "7") (pinfunction "7_7") (pintype "passive"))
      (node (ref "SW1") (pin "8") (pinfunction "8_8") (pintype "passive"))
      (node (ref "U$1") (pin "VCC") (pinfunction "VCC_VCC") (pintype "bidirectional"))
      (node (ref "U$10") (pin "VCC") (pinfunction "VCC_VCC") (pintype "bidirectional"))
      (node (ref "U$12") (pin "VCC") (pinfunction "VCC_VCC") (pintype "bidirectional"))
      (node (ref "U$15") (pin "VCC") (pinfunction "VCC_VCC") (pintype "bidirectional"))
      (node (ref "U$16") (pin "VCC") (pinfunction "VCC_VCC") (pintype "bidirectional"))
      (node (ref "U$17") (pin "VCC") (pinfunction "VCC_VCC") (pintype "bidirectional"))
      (node (ref "U$18") (pin "COM") (pinfunction "COM_COM") (pintype "bidirectional"))
      (node (ref "U$3") (pin "VCC") (pinfunction "VCC_VCC") (pintype "bidirectional"))
      (node (ref "U$4") (pin "OUT+") (pinfunction "VOUT_OUT+") (pintype "bidirectional"))
      (node (ref "U$6") (pin "VCC") (pinfunction "VCC_VCC") (pintype "bidirectional"))
      (node (ref "U$7") (pin "VCC") (pinfunction "VCC_VCC") (pintype "bidirectional"))
      (node (ref "U$8") (pin "VCC") (pinfunction "VCC_VCC") (pintype "bidirectional"))
      (node (ref "U$9") (pin "VCC") (pinfunction "VCC_VCC") (pintype "bidirectional"))
    )
    (net (code "115") (name "unconnected-(ARDUINO-MEGA-20-SDA-Pad20)") (class "Default")
      (node (ref "ARDUINO-MEGA") (pin "20") (pinfunction "20-SDA_20") (pintype "bidirectional"))
    )
    (net (code "116") (name "unconnected-(ARDUINO-MEGA-21-SCL-Pad21)") (class "Default")
      (node (ref "ARDUINO-MEGA") (pin "21") (pinfunction "21-SCL_21") (pintype "bidirectional"))
    )
    (net (code "117") (name "unconnected-(ARDUINO-MEGA-Pad0-RX0)") (class "Default")
      (node (ref "ARDUINO-MEGA") (pin "0-RX0") (pinfunction "0-RX0_0-RX0") (pintype "bidirectional"))
    )
    (net (code "118") (name "unconnected-(ARDUINO-MEGA-Pad1-TX0)") (class "Default")
      (node (ref "ARDUINO-MEGA") (pin "1-TX0") (pinfunction "1-TX0_1-TX0") (pintype "bidirectional"))
    )
    (net (code "119") (name "unconnected-(ARDUINO-MEGA-Pad2)") (class "Default")
      (node (ref "ARDUINO-MEGA") (pin "2") (pinfunction "2_2") (pintype "bidirectional"))
    )
    (net (code "120") (name "unconnected-(ARDUINO-MEGA-Pad3)") (class "Default")
      (node (ref "ARDUINO-MEGA") (pin "3") (pinfunction "3_3") (pintype "bidirectional"))
    )
    (net (code "121") (name "unconnected-(ARDUINO-MEGA-Pad3V3)") (class "Default")
      (node (ref "ARDUINO-MEGA") (pin "3V3") (pinfunction "3V3_3V3") (pintype "bidirectional"))
    )
    (net (code "122") (name "unconnected-(ARDUINO-MEGA-Pad4)") (class "Default")
      (node (ref "ARDUINO-MEGA") (pin "4") (pinfunction "4_4") (pintype "bidirectional"))
    )
    (net (code "123") (name "unconnected-(ARDUINO-MEGA-Pad5)") (class "Default")
      (node (ref "ARDUINO-MEGA") (pin "5") (pinfunction "5_5") (pintype "bidirectional"))
    )
    (net (code "124") (name "unconnected-(ARDUINO-MEGA-Pad5V_1)") (class "Default")
      (node (ref "ARDUINO-MEGA") (pin "5V_1") (pinfunction "5V_1_5V_1") (pintype "bidirectional"))
    )
    (net (code "125") (name "unconnected-(ARDUINO-MEGA-Pad5V_2)") (class "Default")
      (node (ref "ARDUINO-MEGA") (pin "5V_2") (pinfunction "5V_2_5V_2") (pintype "bidirectional"))
    )
    (net (code "126") (name "unconnected-(ARDUINO-MEGA-Pad5V_3)") (class "Default")
      (node (ref "ARDUINO-MEGA") (pin "5V_3") (pinfunction "5V_3_5V_3") (pintype "bidirectional"))
    )
    (net (code "127") (name "unconnected-(ARDUINO-MEGA-Pad14-TX3)") (class "Default")
      (node (ref "ARDUINO-MEGA") (pin "14-TX3") (pinfunction "14-TX3_14-TX3") (pintype "bidirectional"))
    )
    (net (code "128") (name "unconnected-(ARDUINO-MEGA-Pad15-RX3)") (class "Default")
      (node (ref "ARDUINO-MEGA") (pin "15-RX3") (pinfunction "15-RX3_15-RX3") (pintype "bidirectional"))
    )
    (net (code "129") (name "unconnected-(ARDUINO-MEGA-Pad16-TX2)") (class "Default")
      (node (ref "ARDUINO-MEGA") (pin "16-TX2") (pinfunction "16-TX2_16-TX2") (pintype "bidirectional"))
    )
    (net (code "130") (name "unconnected-(ARDUINO-MEGA-Pad17-RX2)") (class "Default")
      (node (ref "ARDUINO-MEGA") (pin "17-RX2") (pinfunction "17-RX2_17-RX2") (pintype "bidirectional"))
    )
    (net (code "131") (name "unconnected-(ARDUINO-MEGA-Pad18-TX1)") (class "Default")
      (node (ref "ARDUINO-MEGA") (pin "18-TX1") (pinfunction "18-TX1_18-TX1") (pintype "bidirectional"))
    )
    (net (code "132") (name "unconnected-(ARDUINO-MEGA-Pad19-RX1)") (class "Default")
      (node (ref "ARDUINO-MEGA") (pin "19-RX1") (pinfunction "19-RX1_19-RX1") (pintype "bidirectional"))
    )
    (net (code "133") (name "unconnected-(ARDUINO-MEGA-Pad22)") (class "Default")
      (node (ref "ARDUINO-MEGA") (pin "22") (pinfunction "22_22") (pintype "bidirectional"))
    )
    (net (code "134") (name "unconnected-(ARDUINO-MEGA-Pad23)") (class "Default")
      (node (ref "ARDUINO-MEGA") (pin "23") (pinfunction "23_23") (pintype "bidirectional"))
    )
    (net (code "135") (name "unconnected-(ARDUINO-MEGA-Pad24)") (class "Default")
      (node (ref "ARDUINO-MEGA") (pin "24") (pinfunction "24_24") (pintype "bidirectional"))
    )
    (net (code "136") (name "unconnected-(ARDUINO-MEGA-Pad25)") (class "Default")
      (node (ref "ARDUINO-MEGA") (pin "25") (pinfunction "25_25") (pintype "bidirectional"))
    )
    (net (code "137") (name "unconnected-(ARDUINO-MEGA-Pad26)") (class "Default")
      (node (ref "ARDUINO-MEGA") (pin "26") (pinfunction "26_26") (pintype "bidirectional"))
    )
    (net (code "138") (name "unconnected-(ARDUINO-MEGA-Pad27)") (class "Default")
      (node (ref "ARDUINO-MEGA") (pin "27") (pinfunction "27_27") (pintype "bidirectional"))
    )
    (net (code "139") (name "unconnected-(ARDUINO-MEGA-Pad28)") (class "Default")
      (node (ref "ARDUINO-MEGA") (pin "28") (pinfunction "28_28") (pintype "bidirectional"))
    )
    (net (code "140") (name "unconnected-(ARDUINO-MEGA-Pad29)") (class "Default")
      (node (ref "ARDUINO-MEGA") (pin "29") (pinfunction "29_29") (pintype "bidirectional"))
    )
    (net (code "141") (name "unconnected-(ARDUINO-MEGA-Pad30)") (class "Default")
      (node (ref "ARDUINO-MEGA") (pin "30") (pinfunction "30_30") (pintype "bidirectional"))
    )
    (net (code "142") (name "unconnected-(ARDUINO-MEGA-Pad31)") (class "Default")
      (node (ref "ARDUINO-MEGA") (pin "31") (pinfunction "31_31") (pintype "bidirectional"))
    )
    (net (code "143") (name "unconnected-(ARDUINO-MEGA-Pad32)") (class "Default")
      (node (ref "ARDUINO-MEGA") (pin "32") (pinfunction "32_32") (pintype "bidirectional"))
    )
    (net (code "144") (name "unconnected-(ARDUINO-MEGA-Pad33)") (class "Default")
      (node (ref "ARDUINO-MEGA") (pin "33") (pinfunction "33_33") (pintype "bidirectional"))
    )
    (net (code "145") (name "unconnected-(ARDUINO-MEGA-Pad34)") (class "Default")
      (node (ref "ARDUINO-MEGA") (pin "34") (pinfunction "34_34") (pintype "bidirectional"))
    )
    (net (code "146") (name "unconnected-(ARDUINO-MEGA-Pad35)") (class "Default")
      (node (ref "ARDUINO-MEGA") (pin "35") (pinfunction "35_35") (pintype "bidirectional"))
    )
    (net (code "147") (name "unconnected-(ARDUINO-MEGA-Pad36)") (class "Default")
      (node (ref "ARDUINO-MEGA") (pin "36") (pinfunction "36_36") (pintype "bidirectional"))
    )
    (net (code "148") (name "unconnected-(ARDUINO-MEGA-Pad37)") (class "Default")
      (node (ref "ARDUINO-MEGA") (pin "37") (pinfunction "37_37") (pintype "bidirectional"))
    )
    (net (code "149") (name "unconnected-(ARDUINO-MEGA-Pad38)") (class "Default")
      (node (ref "ARDUINO-MEGA") (pin "38") (pinfunction "38_38") (pintype "bidirectional"))
    )
    (net (code "150") (name "unconnected-(ARDUINO-MEGA-Pad39)") (class "Default")
      (node (ref "ARDUINO-MEGA") (pin "39") (pinfunction "39_39") (pintype "bidirectional"))
    )
    (net (code "151") (name "unconnected-(ARDUINO-MEGA-Pad40)") (class "Default")
      (node (ref "ARDUINO-MEGA") (pin "40") (pinfunction "40_40") (pintype "bidirectional"))
    )
    (net (code "152") (name "unconnected-(ARDUINO-MEGA-Pad41)") (class "Default")
      (node (ref "ARDUINO-MEGA") (pin "41") (pinfunction "41_41") (pintype "bidirectional"))
    )
    (net (code "153") (name "unconnected-(ARDUINO-MEGA-Pad42)") (class "Default")
      (node (ref "ARDUINO-MEGA") (pin "42") (pinfunction "42_42") (pintype "bidirectional"))
    )
    (net (code "154") (name "unconnected-(ARDUINO-MEGA-Pad43)") (class "Default")
      (node (ref "ARDUINO-MEGA") (pin "43") (pinfunction "43_43") (pintype "bidirectional"))
    )
    (net (code "155") (name "unconnected-(ARDUINO-MEGA-Pad44)") (class "Default")
      (node (ref "ARDUINO-MEGA") (pin "44") (pinfunction "44_44") (pintype "bidirectional"))
    )
    (net (code "156") (name "unconnected-(ARDUINO-MEGA-Pad45)") (class "Default")
      (node (ref "ARDUINO-MEGA") (pin "45") (pinfunction "45_45") (pintype "bidirectional"))
    )
    (net (code "157") (name "unconnected-(ARDUINO-MEGA-Pad46)") (class "Default")
      (node (ref "ARDUINO-MEGA") (pin "46") (pinfunction "46_46") (pintype "bidirectional"))
    )
    (net (code "158") (name "unconnected-(ARDUINO-MEGA-Pad47)") (class "Default")
      (node (ref "ARDUINO-MEGA") (pin "47") (pinfunction "47_47") (pintype "bidirectional"))
    )
    (net (code "159") (name "unconnected-(ARDUINO-MEGA-Pad48)") (class "Default")
      (node (ref "ARDUINO-MEGA") (pin "48") (pinfunction "48_48") (pintype "bidirectional"))
    )
    (net (code "160") (name "unconnected-(ARDUINO-MEGA-Pad49)") (class "Default")
      (node (ref "ARDUINO-MEGA") (pin "49") (pinfunction "49_49") (pintype "bidirectional"))
    )
    (net (code "161") (name "unconnected-(ARDUINO-MEGA-Pad50)") (class "Default")
      (node (ref "ARDUINO-MEGA") (pin "50") (pinfunction "50_50") (pintype "bidirectional"))
    )
    (net (code "162") (name "unconnected-(ARDUINO-MEGA-Pad51)") (class "Default")
      (node (ref "ARDUINO-MEGA") (pin "51") (pinfunction "51_51") (pintype "bidirectional"))
    )
    (net (code "163") (name "unconnected-(ARDUINO-MEGA-Pad52)") (class "Default")
      (node (ref "ARDUINO-MEGA") (pin "52") (pinfunction "52_52") (pintype "bidirectional"))
    )
    (net (code "164") (name "unconnected-(ARDUINO-MEGA-Pad53)") (class "Default")
      (node (ref "ARDUINO-MEGA") (pin "53") (pinfunction "53_53") (pintype "bidirectional"))
    )
    (net (code "165") (name "unconnected-(ARDUINO-MEGA-PadA0)") (class "Default")
      (node (ref "ARDUINO-MEGA") (pin "A0") (pinfunction "A0_A0") (pintype "bidirectional"))
    )
    (net (code "166") (name "unconnected-(ARDUINO-MEGA-PadA1)") (class "Default")
      (node (ref "ARDUINO-MEGA") (pin "A1") (pinfunction "A1_A1") (pintype "bidirectional"))
    )
    (net (code "167") (name "unconnected-(ARDUINO-MEGA-PadA2)") (class "Default")
      (node (ref "ARDUINO-MEGA") (pin "A2") (pinfunction "A2_A2") (pintype "bidirectional"))
    )
    (net (code "168") (name "unconnected-(ARDUINO-MEGA-PadA3)") (class "Default")
      (node (ref "ARDUINO-MEGA") (pin "A3") (pinfunction "A3_A3") (pintype "bidirectional"))
    )
    (net (code "169") (name "unconnected-(ARDUINO-MEGA-PadA4)") (class "Default")
      (node (ref "ARDUINO-MEGA") (pin "A4") (pinfunction "A4_A4") (pintype "bidirectional"))
    )
    (net (code "170") (name "unconnected-(ARDUINO-MEGA-PadA5)") (class "Default")
      (node (ref "ARDUINO-MEGA") (pin "A5") (pinfunction "A5_A5") (pintype "bidirectional"))
    )
    (net (code "171") (name "unconnected-(ARDUINO-MEGA-PadA6)") (class "Default")
      (node (ref "ARDUINO-MEGA") (pin "A6") (pinfunction "A6_A6") (pintype "bidirectional"))
    )
    (net (code "172") (name "unconnected-(ARDUINO-MEGA-PadA7)") (class "Default")
      (node (ref "ARDUINO-MEGA") (pin "A7") (pinfunction "A7_A7") (pintype "bidirectional"))
    )
    (net (code "173") (name "unconnected-(ARDUINO-MEGA-PadA8)") (class "Default")
      (node (ref "ARDUINO-MEGA") (pin "A8") (pinfunction "A8_A8") (pintype "bidirectional"))
    )
    (net (code "174") (name "unconnected-(ARDUINO-MEGA-PadA9)") (class "Default")
      (node (ref "ARDUINO-MEGA") (pin "A9") (pinfunction "A9_A9") (pintype "bidirectional"))
    )
    (net (code "175") (name "unconnected-(ARDUINO-MEGA-PadA10)") (class "Default")
      (node (ref "ARDUINO-MEGA") (pin "A10") (pinfunction "A10_A10") (pintype "bidirectional"))
    )
    (net (code "176") (name "unconnected-(ARDUINO-MEGA-PadA11)") (class "Default")
      (node (ref "ARDUINO-MEGA") (pin "A11") (pinfunction "A11_A11") (pintype "bidirectional"))
    )
    (net (code "177") (name "unconnected-(ARDUINO-MEGA-PadA12)") (class "Default")
      (node (ref "ARDUINO-MEGA") (pin "A12") (pinfunction "A12_A12") (pintype "bidirectional"))
    )
    (net (code "178") (name "unconnected-(ARDUINO-MEGA-PadA13)") (class "Default")
      (node (ref "ARDUINO-MEGA") (pin "A13") (pinfunction "A13_A13") (pintype "bidirectional"))
    )
    (net (code "179") (name "unconnected-(ARDUINO-MEGA-PadA14)") (class "Default")
      (node (ref "ARDUINO-MEGA") (pin "A14") (pinfunction "A14_A14") (pintype "bidirectional"))
    )
    (net (code "180") (name "unconnected-(ARDUINO-MEGA-PadA15)") (class "Default")
      (node (ref "ARDUINO-MEGA") (pin "A15") (pinfunction "A15_A15") (pintype "bidirectional"))
    )
    (net (code "181") (name "unconnected-(ARDUINO-MEGA-PadGND_1)") (class "Default")
      (node (ref "ARDUINO-MEGA") (pin "GND_1") (pinfunction "GND_1_GND_1") (pintype "bidirectional"))
    )
    (net (code "182") (name "unconnected-(ARDUINO-MEGA-PadGND_2)") (class "Default")
      (node (ref "ARDUINO-MEGA") (pin "GND_2") (pinfunction "GND_2_GND_2") (pintype "bidirectional"))
    )
    (net (code "183") (name "unconnected-(ARDUINO-MEGA-PadGND_3)") (class "Default")
      (node (ref "ARDUINO-MEGA") (pin "GND_3") (pinfunction "GND_3_GND_3") (pintype "bidirectional"))
    )
    (net (code "184") (name "unconnected-(ARDUINO-MEGA-PadGND_4)") (class "Default")
      (node (ref "ARDUINO-MEGA") (pin "GND_4") (pinfunction "GND_4_GND_4") (pintype "bidirectional"))
    )
    (net (code "185") (name "unconnected-(ARDUINO-MEGA-PadIOREF)") (class "Default")
      (node (ref "ARDUINO-MEGA") (pin "IOREF") (pinfunction "IOREF_IOREF") (pintype "bidirectional"))
    )
    (net (code "186") (name "unconnected-(ARDUINO-MEGA-PadNC)") (class "Default")
      (node (ref "ARDUINO-MEGA") (pin "NC") (pinfunction "NC_NC") (pintype "bidirectional"))
    )
    (net (code "187") (name "unconnected-(ARDUINO-MEGA-PadSCL)") (class "Default")
      (node (ref "ARDUINO-MEGA") (pin "SCL") (pinfunction "SCL_SCL") (pintype "bidirectional"))
    )
    (net (code "188") (name "unconnected-(ARDUINO-MEGA-PadVIN)") (class "Default")
      (node (ref "ARDUINO-MEGA") (pin "VIN") (pinfunction "VIN_VIN") (pintype "bidirectional"))
    )
    (net (code "189") (name "unconnected-(HC-05-PadEN)") (class "Default")
      (node (ref "HC-05") (pin "EN") (pinfunction "EN_EN") (pintype "bidirectional"))
    )
    (net (code "190") (name "unconnected-(HC-05-PadSTATE)") (class "Default")
      (node (ref "HC-05") (pin "STATE") (pinfunction "STATE_STATE") (pintype "bidirectional"))
    )
    (net (code "191") (name "unconnected-(S1-S1-Pad2)") (class "Default")
      (node (ref "S1") (pin "2") (pinfunction "S1_2") (pintype "passive"))
    )
    (net (code "192") (name "unconnected-(S2-S1-Pad2)") (class "Default")
      (node (ref "S2") (pin "2") (pinfunction "S1_2") (pintype "passive"))
    )
    (net (code "193") (name "unconnected-(S3-S1-Pad2)") (class "Default")
      (node (ref "S3") (pin "2") (pinfunction "S1_2") (pintype "passive"))
    )
    (net (code "194") (name "unconnected-(S4-S1-Pad2)") (class "Default")
      (node (ref "S4") (pin "2") (pinfunction "S1_2") (pintype "passive"))
    )
    (net (code "195") (name "unconnected-(U$2-PadCOM)") (class "Default")
      (node (ref "U$2") (pin "COM") (pinfunction "COM_COM") (pintype "bidirectional"))
    )
    (net (code "196") (name "unconnected-(U$2-PadP1)") (class "Default")
      (node (ref "U$2") (pin "P1") (pinfunction "P1_P1") (pintype "bidirectional"))
    )
    (net (code "197") (name "unconnected-(U$3-PadSTBY)") (class "Default")
      (node (ref "U$3") (pin "STBY") (pinfunction "STBY_STBY") (pintype "bidirectional"))
    )
    (net (code "198") (name "unconnected-(U$6-PadSTBY)") (class "Default")
      (node (ref "U$6") (pin "STBY") (pinfunction "STBY_STBY") (pintype "bidirectional"))
    )
    (net (code "199") (name "unconnected-(U$18-PadP1)") (class "Default")
      (node (ref "U$18") (pin "P1") (pinfunction "P1_P1") (pintype "bidirectional"))
    )
  )
)
